# untitled.net
KiCad netlist of a schematic drawn in EAGLE
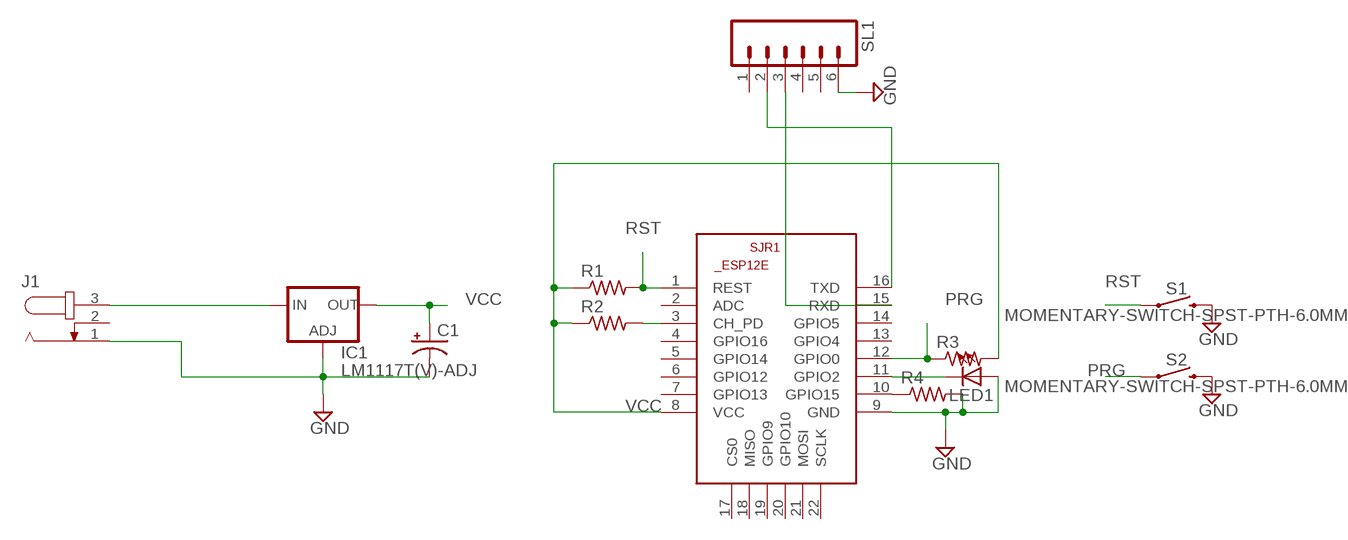
[diagram p0: schematic, sheet 1]

(export (version "E")
  (design (tool "Eeschema 10.0.6"))
  (components
    (comp (ref "C1")
      (value "CAPACITOR-PE5-10.5")
      (footprint "eagle-import:E5-10,5")
      (libsource (lib "eagle-import") (part "CAPACITOR-PE5-10.5"))
    )
    (comp (ref "IC1")
      (value "LM1117T(V)-ADJ")
      (footprint "eagle-import:TO220V")
      (fields (field (name "MF") "Texas Instruments") (field (name "MPN") "LM1777T-ADJ"))
      (libsource (lib "eagle-import") (part "LM1117?-ADJT(V)"))
    )
    (comp (ref "J1")
      (value "JACK-PLUG1")
      (footprint "eagle-import:SPC4078")
      (libsource (lib "eagle-import") (part "JACK-PLUG1"))
    )
    (comp (ref "LED1")
      (value "LED5MM")
      (footprint "eagle-import:LED5MM")
      (libsource (lib "eagle-import") (part "LED5MM"))
    )
    (comp (ref "R1")
      (value "R-US_0207/10")
      (footprint "eagle-import:0207_10")
      (libsource (lib "eagle-import") (part "R-US_0207/10"))
    )
    (comp (ref "R2")
      (value "R-US_0207/10")
      (footprint "eagle-import:0207_10")
      (libsource (lib "eagle-import") (part "R-US_0207/10"))
    )
    (comp (ref "R3")
      (value "R-US_0207/10")
      (footprint "eagle-import:0207_10")
      (libsource (lib "eagle-import") (part "R-US_0207/10"))
    )
    (comp (ref "R4")
      (value "R-US_0207/10")
      (footprint "eagle-import:0207_10")
      (libsource (lib "eagle-import") (part "R-US_0207/10"))
    )
    (comp (ref "S1")
      (value "MOMENTARY-SWITCH-SPST-PTH-6.0MM")
      (footprint "eagle-import:TACTILE_SWITCH_PTH_6.0MM")
      (libsource (lib "eagle-import") (part "MOMENTARY-SWITCH-SPST-PTH-6.0MM"))
    )
    (comp (ref "S2")
      (value "MOMENTARY-SWITCH-SPST-PTH-6.0MM")
      (footprint "eagle-import:TACTILE_SWITCH_PTH_6.0MM")
      (libsource (lib "eagle-import") (part "MOMENTARY-SWITCH-SPST-PTH-6.0MM"))
    )
    (comp (ref "SJR1")
      (value "ESP8266-12EESP12E")
      (footprint "eagle-import:ESP8266-ESP12E")
      (libsource (lib "eagle-import") (part "ESP8266-12EESP12E"))
    )
    (comp (ref "SL1")
      (value "M06")
      (footprint "eagle-import:06P")
      (libsource (lib "eagle-import") (part "M06"))
    )
  )
  (nets
    (net (code "1") (name "/PRG") (class "Default")
      (node (ref "R3") (pin "1") (pinfunction "1_1") (pintype "passive"))
      (node (ref "S2") (pin "1") (pinfunction "1_1") (pintype "passive"))
      (node (ref "SJR1") (pin "12") (pinfunction "GPIO0_12") (pintype "bidirectional"))
    )
    (net (code "2") (name "/RST") (class "Default")
      (node (ref "R1") (pin "2") (pinfunction "2_2") (pintype "passive"))
      (node (ref "S1") (pin "1") (pinfunction "1_1") (pintype "passive"))
      (node (ref "SJR1") (pin "1") (pinfunction "REST_1") (pintype "bidirectional"))
    )
    (net (code "3") (name "/VCC") (class "Default")
      (node (ref "C1") (pin "+") (pinfunction "+_+") (pintype "passive"))
      (node (ref "IC1") (pin "2") (pinfunction "OUT_2") (pintype "passive"))
      (node (ref "R1") (pin "1") (pinfunction "1_1") (pintype "passive"))
      (node (ref "R2") (pin "1") (pinfunction "1_1") (pintype "passive"))
      (node (ref "R3") (pin "2") (pinfunction "2_2") (pintype "passive"))
      (node (ref "SJR1") (pin "8") (pinfunction "VCC_8") (pintype "bidirectional"))
    )
    (net (code "4") (name "GND") (class "Default")
      (node (ref "C1") (pin "-") (pinfunction "-_-") (pintype "passive"))
      (node (ref "IC1") (pin "1") (pinfunction "ADJ_1") (pintype "input"))
      (node (ref "J1") (pin "1") (pinfunction "1_1") (pintype "passive"))
      (node (ref "LED1") (pin "A") (pinfunction "A_A") (pintype "passive"))
      (node (ref "R4") (pin "2") (pinfunction "2_2") (pintype "passive"))
      (node (ref "S1") (pin "3") (pinfunction "2_3") (pintype "passive"))
      (node (ref "S2") (pin "3") (pinfunction "2_3") (pintype "passive"))
      (node (ref "SJR1") (pin "9") (pinfunction "GND_9") (pintype "bidirectional"))
      (node (ref "SL1") (pin "6") (pinfunction "6_6") (pintype "passive"))
    )
    (net (code "5") (name "Net-(IC1-IN)") (class "Default")
      (node (ref "IC1") (pin "3") (pinfunction "IN_3") (pintype "input"))
      (node (ref "J1") (pin "3") (pinfunction "3_3") (pintype "passive"))
    )
    (net (code "6") (name "Net-(LED1-C)") (class "Default")
      (node (ref "LED1") (pin "K") (pinfunction "C_K") (pintype "passive"))
      (node (ref "SJR1") (pin "11") (pinfunction "GPIO2_11") (pintype "bidirectional"))
    )
    (net (code "7") (name "Net-(SJR1-CH_PD)") (class "Default")
      (node (ref "R2") (pin "2") (pinfunction "2_2") (pintype "passive"))
      (node (ref "SJR1") (pin "3") (pinfunction "CH_PD_3") (pintype "bidirectional"))
    )
    (net (code "8") (name "Net-(SJR1-GPIO15)") (class "Default")
      (node (ref "R4") (pin "1") (pinfunction "1_1") (pintype "passive"))
      (node (ref "SJR1") (pin "10") (pinfunction "GPIO15_10") (pintype "bidirectional"))
    )
    (net (code "9") (name "Net-(SJR1-RXD)") (class "Default")
      (node (ref "SJR1") (pin "15") (pinfunction "RXD_15") (pintype "bidirectional"))
      (node (ref "SL1") (pin "3") (pinfunction "3_3") (pintype "passive"))
    )
    (net (code "10") (name "Net-(SJR1-TXD)") (class "Default")
      (node (ref "SJR1") (pin "16") (pinfunction "TXD_16") (pintype "bidirectional"))
      (node (ref "SL1") (pin "2") (pinfunction "2_2") (pintype "passive"))
    )
    (net (code "11") (name "unconnected-(J1-Pad2)") (class "Default")
      (node (ref "J1") (pin "2") (pinfunction "2_2") (pintype "passive"))
    )
    (net (code "12") (name "unconnected-(SJR1-ADC-Pad2)") (class "Default")
      (node (ref "SJR1") (pin "2") (pinfunction "ADC_2") (pintype "bidirectional"))
    )
    (net (code "13") (name "unconnected-(SJR1-CS0-Pad17)") (class "Default")
      (node (ref "SJR1") (pin "17") (pinfunction "CS0_17") (pintype "bidirectional"))
    )
    (net (code "14") (name "unconnected-(SJR1-GPIO4-Pad13)") (class "Default")
      (node (ref "SJR1") (pin "13") (pinfunction "GPIO4_13") (pintype "bidirectional"))
    )
    (net (code "15") (name "unconnected-(SJR1-GPIO5-Pad14)") (class "Default")
      (node (ref "SJR1") (pin "14") (pinfunction "GPIO5_14") (pintype "bidirectional"))
    )
    (net (code "16") (name "unconnected-(SJR1-GPIO9-Pad19)") (class "Default")
      (node (ref "SJR1") (pin "19") (pinfunction "GPIO9_19") (pintype "bidirectional"))
    )
    (net (code "17") (name "unconnected-(SJR1-GPIO10-Pad20)") (class "Default")
      (node (ref "SJR1") (pin "20") (pinfunction "GPIO10_20") (pintype "bidirectional"))
    )
    (net (code "18") (name "unconnected-(SJR1-GPIO12-Pad6)") (class "Default")
      (node (ref "SJR1") (pin "6") (pinfunction "GPIO12_6") (pintype "bidirectional"))
    )
    (net (code "19") (name "unconnected-(SJR1-GPIO13-Pad7)") (class "Default")
      (node (ref "SJR1") (pin "7") (pinfunction "GPIO13_7") (pintype "bidirectional"))
    )
    (net (code "20") (name "unconnected-(SJR1-GPIO14-Pad5)") (class "Default")
      (node (ref "SJR1") (pin "5") (pinfunction "GPIO14_5") (pintype "bidirectional"))
    )
    (net (code "21") (name "unconnected-(SJR1-GPIO16-Pad4)") (class "Default")
      (node (ref "SJR1") (pin "4") (pinfunction "GPIO16_4") (pintype "bidirectional"))
    )
    (net (code "22") (name "unconnected-(SJR1-MISO-Pad18)") (class "Default")
      (node (ref "SJR1") (pin "18") (pinfunction "MISO_18") (pintype "bidirectional"))
    )
    (net (code "23") (name "unconnected-(SJR1-MOSI-Pad21)") (class "Default")
      (node (ref "SJR1") (pin "21") (pinfunction "MOSI_21") (pintype "bidirectional"))
    )
    (net (code "24") (name "unconnected-(SJR1-SCLK-Pad22)") (class "Default")
      (node (ref "SJR1") (pin "22") (pinfunction "SCLK_22") (pintype "bidirectional"))
    )
    (net (code "25") (name "unconnected-(SL1-Pad1)") (class "Default")
      (node (ref "SL1") (pin "1") (pinfunction "1_1") (pintype "passive"))
    )
    (net (code "26") (name "unconnected-(SL1-Pad4)") (class "Default")
      (node (ref "SL1") (pin "4") (pinfunction "4_4") (pintype "passive"))
    )
    (net (code "27") (name "unconnected-(SL1-Pad5)") (class "Default")
      (node (ref "SL1") (pin "5") (pinfunction "5_5") (pintype "passive"))
    )
  )
)
